# SCH_NFT-Card-Michael_2024-10-10.net
KiCad netlist of a schematic drawn in EasyEDA
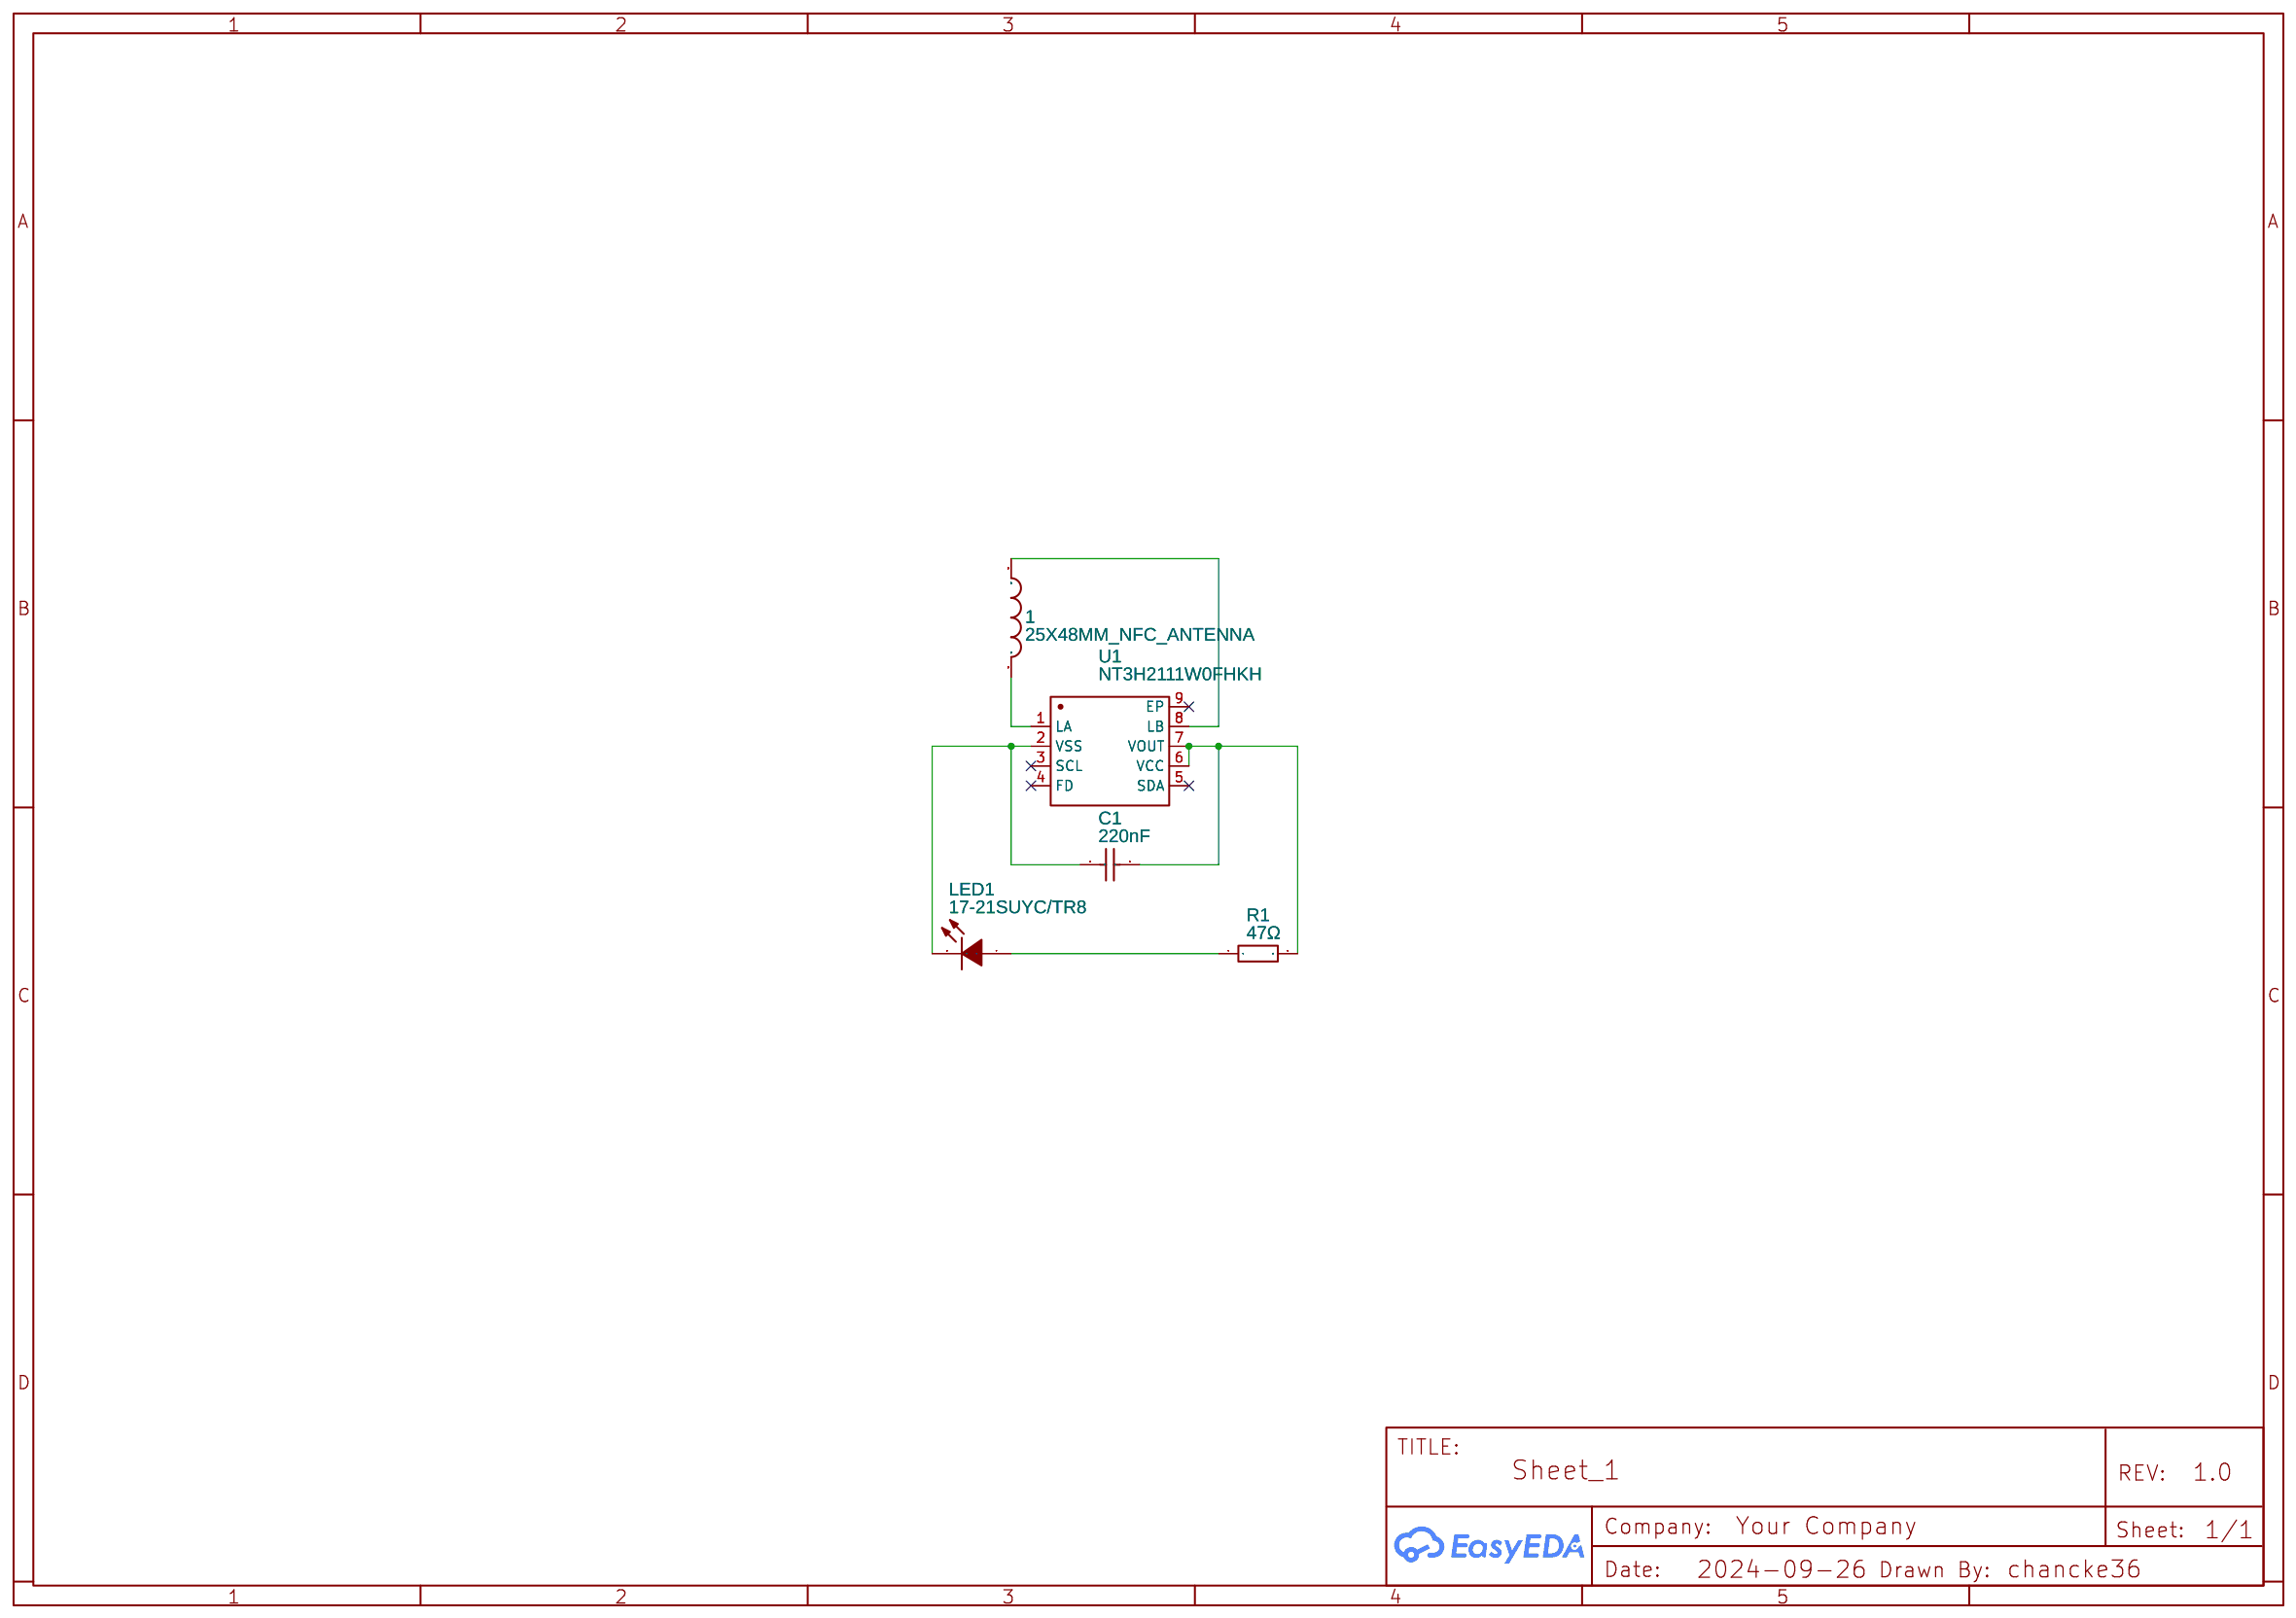
[diagram p0: schematic sheet]

(export (version "E")
  (design (tool "Eeschema 10.0.6"))
  (components
    (comp (ref "1") (value "25X48MM_NFC_ANTENNA") (libsource (lib "") (part "25X48MM_NFC_ANTENNA")))
    (comp (ref "C1")
      (value "220nF")
      (fields
        (field (name "Manufacturer Part") "CL10B224KA8NNNC")
        (field (name "Manufacturer") "SAMSUNG(三星)")
      )
      (libsource (lib "") (part "CL10B224KA8NNNC"))
    )
    (comp (ref "LED1")
      (value "17-21SUYC/TR8")
      (fields (field (name "Manufacturer Part") "KT-0805黄灯") (field (name "Manufacturer") "KENTO"))
      (libsource (lib "") (part "17-21SUYC/TR8"))
    )
    (comp (ref "R1")
      (value "47Ω")
      (fields
        (field (name "Manufacturer Part") "0603WAF470JT5E")
        (field (name "Manufacturer") "UNI-ROYAL(厚声)")
      )
      (libsource (lib "") (part "0603WAF470JT5E"))
    )
    (comp (ref "U1")
      (value "NT3H2111W0FHKH")
      (fields (field (name "Manufacturer") "NXP(恩智浦)"))
      (libsource (lib "") (part "NT3H2111W0FHKH"))
    )
  )
  (nets
    (net (code "1") (name "Net-(LED1-+)") (class "Default")
      (node (ref "LED1") (pin "1") (pinfunction "+_1") (pintype "unspecified"))
      (node (ref "R1") (pin "1") (pinfunction "1_1") (pintype "input"))
    )
    (net (code "2") (name "Net-(LED1--)") (class "Default")
      (node (ref "C1") (pin "1") (pinfunction "1_1") (pintype "input"))
      (node (ref "LED1") (pin "2") (pinfunction "-_2") (pintype "unspecified"))
      (node (ref "U1") (pin "2") (pinfunction "VSS_2") (pintype "unspecified"))
    )
    (net (code "3") (name "Net-(U1-LA)") (class "Default")
      (node (ref "1") (pin "P$2") (pinfunction "P$2_P$2") (pintype "bidirectional"))
      (node (ref "U1") (pin "1") (pinfunction "LA_1") (pintype "unspecified"))
    )
    (net (code "4") (name "Net-(U1-LB)") (class "Default")
      (node (ref "1") (pin "P$1") (pinfunction "P$1_P$1") (pintype "bidirectional"))
      (node (ref "U1") (pin "8") (pinfunction "LB_8") (pintype "unspecified"))
    )
    (net (code "5") (name "Net-(U1-VCC)") (class "Default")
      (node (ref "C1") (pin "2") (pinfunction "2_2") (pintype "input"))
      (node (ref "R1") (pin "2") (pinfunction "2_2") (pintype "input"))
      (node (ref "U1") (pin "6") (pinfunction "VCC_6") (pintype "unspecified"))
      (node (ref "U1") (pin "7") (pinfunction "VOUT_7") (pintype "unspecified"))
    )
    (net (code "6") (name "unconnected-(U1-EP-Pad9)") (class "Default")
      (node (ref "U1") (pin "9") (pinfunction "EP_9") (pintype "unspecified+no_connect"))
    )
    (net (code "7") (name "unconnected-(U1-FD-Pad4)") (class "Default")
      (node (ref "U1") (pin "4") (pinfunction "FD_4") (pintype "unspecified+no_connect"))
    )
    (net (code "8") (name "unconnected-(U1-SCL-Pad3)") (class "Default")
      (node (ref "U1") (pin "3") (pinfunction "SCL_3") (pintype "unspecified+no_connect"))
    )
    (net (code "9") (name "unconnected-(U1-SDA-Pad5)") (class "Default")
      (node (ref "U1") (pin "5") (pinfunction "SDA_5") (pintype "unspecified+no_connect"))
    )
  )
)
